# shoulder.net
KiCad netlist of a schematic drawn in EAGLE
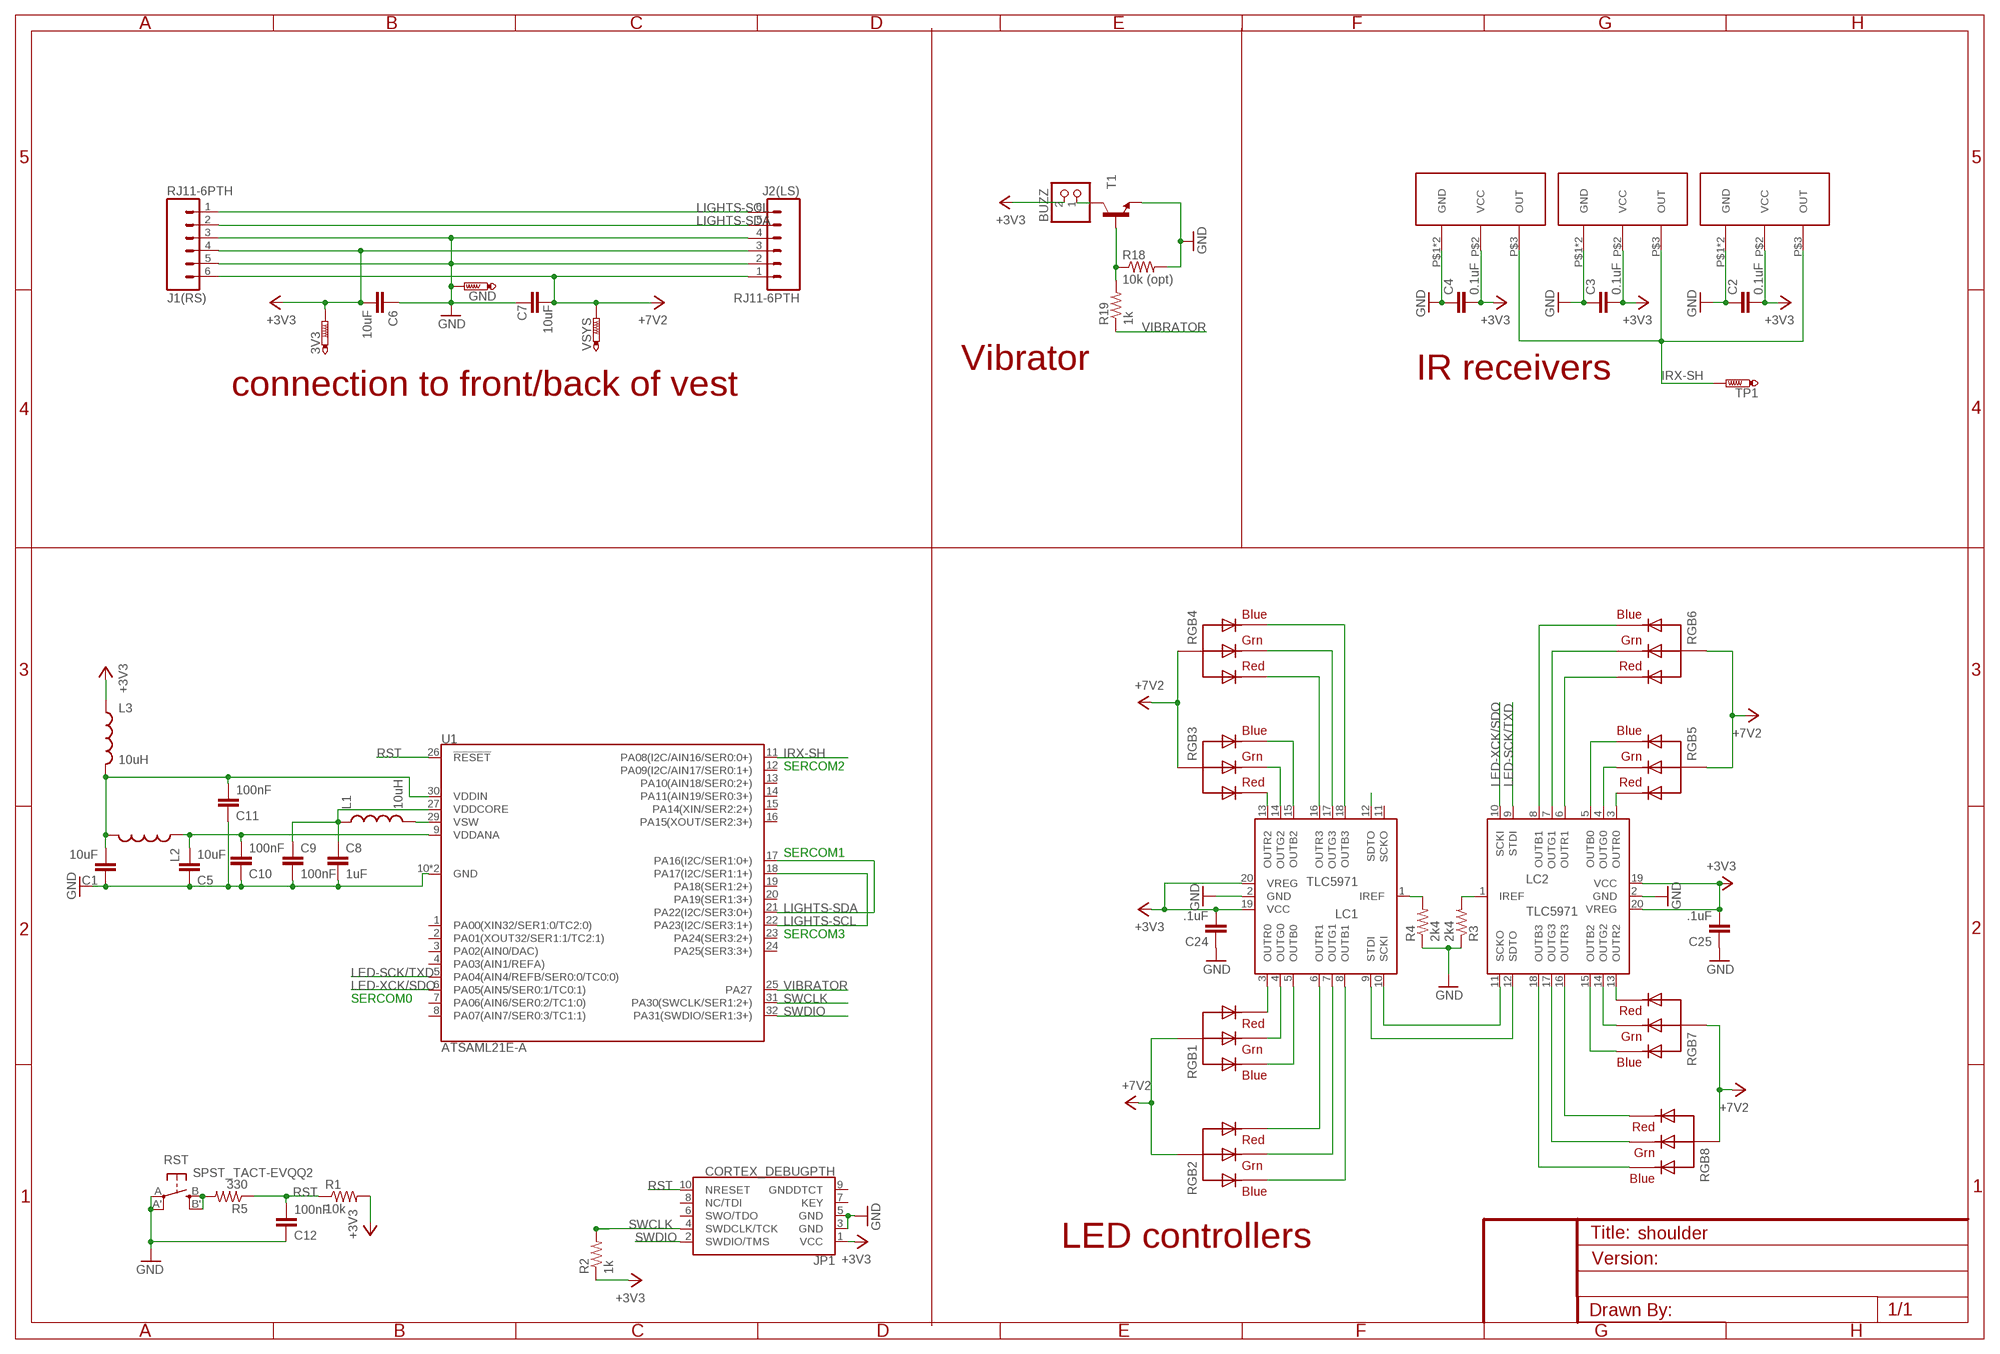
[diagram p0: schematic, sheet 1]

(export (version "E")
  (design (tool "Eeschema 10.0.6"))
  (components
    (comp (ref "3V3")
      (value "PTR1PAD1-17")
      (footprint "eagle-import:P1-17")
      (libsource (lib "eagle-import") (part "PTR1PAD1-17"))
    )
    (comp (ref "BUZZ")
      (value "JST_2PIN-THM")
      (footprint "eagle-import:JST-PH-2-THM")
      (libsource (lib "eagle-import") (part "JST_2PIN-THM"))
    )
    (comp (ref "C1")
      (value "10uF")
      (footprint "eagle-import:0603-CAP")
      (libsource (lib "eagle-import") (part "SparkFun-Passives_CAP0603-CAP"))
    )
    (comp (ref "C2")
      (value "0.1uF")
      (footprint "eagle-import:0603-CAP")
      (libsource (lib "eagle-import") (part "CAP0603-CAP"))
    )
    (comp (ref "C3")
      (value "0.1uF")
      (footprint "eagle-import:0603-CAP")
      (libsource (lib "eagle-import") (part "CAP0603-CAP"))
    )
    (comp (ref "C4")
      (value "0.1uF")
      (footprint "eagle-import:0603-CAP")
      (libsource (lib "eagle-import") (part "CAP0603-CAP"))
    )
    (comp (ref "C5")
      (value "10uF")
      (footprint "eagle-import:0603-CAP")
      (libsource (lib "eagle-import") (part "SparkFun-Passives_CAP0603-CAP"))
    )
    (comp (ref "C6")
      (value "10uF")
      (footprint "eagle-import:1206")
      (libsource (lib "eagle-import") (part "SparkFun-Passives_CAP1206"))
    )
    (comp (ref "C7")
      (value "10uF")
      (footprint "eagle-import:1206")
      (libsource (lib "eagle-import") (part "SparkFun-Passives_CAP1206"))
    )
    (comp (ref "C8")
      (value "1uF")
      (footprint "eagle-import:0603-CAP")
      (libsource (lib "eagle-import") (part "SparkFun-Passives_CAP0603-CAP"))
    )
    (comp (ref "C9")
      (value "100nF")
      (footprint "eagle-import:0603-CAP")
      (libsource (lib "eagle-import") (part "SparkFun-Passives_CAP0603-CAP"))
    )
    (comp (ref "C10")
      (value "100nF")
      (footprint "eagle-import:0603-CAP")
      (libsource (lib "eagle-import") (part "SparkFun-Passives_CAP0603-CAP"))
    )
    (comp (ref "C11")
      (value "100nF")
      (footprint "eagle-import:0603-CAP")
      (libsource (lib "eagle-import") (part "SparkFun-Passives_CAP0603-CAP"))
    )
    (comp (ref "C12")
      (value "100nF")
      (footprint "eagle-import:0603-CAP")
      (libsource (lib "eagle-import") (part "SparkFun-Passives_CAP0603-CAP"))
    )
    (comp (ref "C24")
      (value ".1uF")
      (footprint "eagle-import:0603-CAP")
      (libsource (lib "eagle-import") (part "CAP0603-CAP"))
    )
    (comp (ref "C25")
      (value ".1uF")
      (footprint "eagle-import:0603-CAP")
      (libsource (lib "eagle-import") (part "CAP0603-CAP"))
    )
    (comp (ref "GND")
      (value "PTR1PAD1-17")
      (footprint "eagle-import:P1-17")
      (libsource (lib "eagle-import") (part "PTR1PAD1-17"))
    )
    (comp (ref "J1(RS)")
      (value "RJ11-6PTH")
      (footprint "eagle-import:RJ11-6")
      (libsource (lib "eagle-import") (part "RJ11-6PTH"))
    )
    (comp (ref "J2(LS)")
      (value "RJ11-6PTH")
      (footprint "eagle-import:RJ11-6")
      (libsource (lib "eagle-import") (part "RJ11-6PTH"))
    )
    (comp (ref "JP1")
      (value "CORTEX_DEBUGPTH")
      (footprint "eagle-import:2X5-PTH-1.27MM")
      (libsource (lib "eagle-import") (part "CORTEX_DEBUGPTH"))
    )
    (comp (ref "L1")
      (value "10uH")
      (footprint "eagle-import:0805")
      (libsource (lib "eagle-import") (part "INDUCTOR0805"))
    )
    (comp (ref "L2")
      (value "INDUCTOR0603")
      (footprint "eagle-import:0603")
      (libsource (lib "eagle-import") (part "INDUCTOR0603"))
    )
    (comp (ref "L3")
      (value "10uH")
      (footprint "eagle-import:0805")
      (libsource (lib "eagle-import") (part "INDUCTOR0805"))
    )
    (comp (ref "LC1")
      (value "TLC5971")
      (footprint "eagle-import:SSOP20")
      (libsource (lib "eagle-import") (part "TLC5971"))
    )
    (comp (ref "LC2")
      (value "TLC5971")
      (footprint "eagle-import:SSOP20")
      (libsource (lib "eagle-import") (part "TLC5971"))
    )
    (comp (ref "R1")
      (value "10k")
      (footprint "eagle-import:0603-RES")
      (libsource (lib "eagle-import") (part "RESISTOR0603-RES"))
    )
    (comp (ref "R2")
      (value "1k")
      (footprint "eagle-import:0603-RES")
      (libsource (lib "eagle-import") (part "RESISTOR0603-RES"))
    )
    (comp (ref "R3")
      (value "2k4")
      (footprint "eagle-import:0603-RES")
      (libsource (lib "eagle-import") (part "RESISTOR0603-RES"))
    )
    (comp (ref "R4")
      (value "2k4")
      (footprint "eagle-import:0603-RES")
      (libsource (lib "eagle-import") (part "RESISTOR0603-RES"))
    )
    (comp (ref "R5")
      (value "330")
      (footprint "eagle-import:0603-RES")
      (libsource (lib "eagle-import") (part "RESISTOR0603-RES"))
    )
    (comp (ref "R18")
      (value "10k (opt)")
      (footprint "eagle-import:0603-RES")
      (libsource (lib "eagle-import") (part "RESISTOR0603-RES"))
    )
    (comp (ref "R19")
      (value "1k")
      (footprint "eagle-import:0603-RES")
      (libsource (lib "eagle-import") (part "RESISTOR0603-RES"))
    )
    (comp (ref "RGB1")
      (value "AVAGO-RGB-SMT")
      (footprint "eagle-import:AVAGO-SMT-RGB")
      (libsource (lib "eagle-import") (part "AVAGO-RGB-SMT"))
    )
    (comp (ref "RGB2")
      (value "AVAGO-RGB-SMT")
      (footprint "eagle-import:AVAGO-SMT-RGB")
      (libsource (lib "eagle-import") (part "AVAGO-RGB-SMT"))
    )
    (comp (ref "RGB3")
      (value "AVAGO-RGB-SMT")
      (footprint "eagle-import:AVAGO-SMT-RGB")
      (libsource (lib "eagle-import") (part "AVAGO-RGB-SMT"))
    )
    (comp (ref "RGB4")
      (value "AVAGO-RGB-SMT")
      (footprint "eagle-import:AVAGO-SMT-RGB")
      (libsource (lib "eagle-import") (part "AVAGO-RGB-SMT"))
    )
    (comp (ref "RGB5")
      (value "AVAGO-RGB-SMT")
      (footprint "eagle-import:AVAGO-SMT-RGB")
      (libsource (lib "eagle-import") (part "AVAGO-RGB-SMT"))
    )
    (comp (ref "RGB6")
      (value "AVAGO-RGB-SMT")
      (footprint "eagle-import:AVAGO-SMT-RGB")
      (libsource (lib "eagle-import") (part "AVAGO-RGB-SMT"))
    )
    (comp (ref "RGB7")
      (value "AVAGO-RGB-SMT")
      (footprint "eagle-import:AVAGO-SMT-RGB")
      (libsource (lib "eagle-import") (part "AVAGO-RGB-SMT"))
    )
    (comp (ref "RGB8")
      (value "AVAGO-RGB-SMT")
      (footprint "eagle-import:AVAGO-SMT-RGB")
      (libsource (lib "eagle-import") (part "AVAGO-RGB-SMT"))
    )
    (comp (ref "RST")
      (value "SPST_TACT-EVQQ2")
      (footprint "eagle-import:EVQ-Q2")
      (libsource (lib "eagle-import") (part "SPST_TACT-EVQQ2"))
    )
    (comp (ref "T1")
      (value "TRANSISTOR_NPNSOT23")
      (footprint "eagle-import:SOT23")
      (libsource (lib "eagle-import") (part "TRANSISTOR_NPNSOT23"))
    )
    (comp (ref "TP1")
      (value "PTR1PAD1-17")
      (footprint "eagle-import:P1-17")
      (libsource (lib "eagle-import") (part "PTR1PAD1-17"))
    )
    (comp (ref "U$1")
      (value "TSMP77000SIDE")
      (footprint "eagle-import:TSMP77000")
      (libsource (lib "eagle-import") (part "TSMP77000SIDE"))
    )
    (comp (ref "U$2")
      (value "TSMP77000SIDE")
      (footprint "eagle-import:TSMP77000")
      (libsource (lib "eagle-import") (part "TSMP77000SIDE"))
    )
    (comp (ref "U$3")
      (value "TSMP77000UP")
      (footprint "eagle-import:HEIMDALL-UP")
      (libsource (lib "eagle-import") (part "TSMP77000UP"))
    )
    (comp (ref "U1")
      (value "ATSAML21E-A")
      (footprint "eagle-import:TQFP-32-7X7-0.8MM")
      (libsource (lib "eagle-import") (part "ATSAML21E-A"))
    )
    (comp (ref "VSYS")
      (value "PTR1PAD1-17")
      (footprint "eagle-import:P1-17")
      (libsource (lib "eagle-import") (part "PTR1PAD1-17"))
    )
  )
  (nets
    (net (code "1") (name "+3V3") (class "Default")
      (node (ref "3V3") (pin "TP") (pinfunction "TP_TP") (pintype "input"))
      (node (ref "BUZZ") (pin "2") (pinfunction "1_2") (pintype "passive"))
      (node (ref "C2") (pin "2") (pinfunction "2_2") (pintype "passive"))
      (node (ref "C24") (pin "2") (pinfunction "2_2") (pintype "passive"))
      (node (ref "C25") (pin "2") (pinfunction "2_2") (pintype "passive"))
      (node (ref "C3") (pin "2") (pinfunction "2_2") (pintype "passive"))
      (node (ref "C4") (pin "2") (pinfunction "2_2") (pintype "passive"))
      (node (ref "C6") (pin "2") (pinfunction "2_2") (pintype "passive"))
      (node (ref "J1(RS)") (pin "4") (pinfunction "4_4") (pintype "passive"))
      (node (ref "J2(LS)") (pin "3") (pinfunction "3_3") (pintype "passive"))
      (node (ref "JP1") (pin "1") (pinfunction "VCC_1") (pintype "bidirectional"))
      (node (ref "L3") (pin "1") (pinfunction "1_1") (pintype "passive"))
      (node (ref "LC1") (pin "19") (pinfunction "VCC_19") (pintype "power_in"))
      (node (ref "LC1") (pin "20") (pinfunction "VREG_20") (pintype "passive"))
      (node (ref "LC2") (pin "19") (pinfunction "VCC_19") (pintype "power_in"))
      (node (ref "LC2") (pin "20") (pinfunction "VREG_20") (pintype "passive"))
      (node (ref "R1") (pin "2") (pinfunction "2_2") (pintype "passive"))
      (node (ref "R2") (pin "1") (pinfunction "1_1") (pintype "passive"))
      (node (ref "U$1") (pin "P$2") (pinfunction "VCC_P$2") (pintype "passive"))
      (node (ref "U$2") (pin "P$2") (pinfunction "VCC_P$2") (pintype "passive"))
      (node (ref "U$3") (pin "P$2") (pinfunction "VCC_P$2") (pintype "passive"))
    )
    (net (code "2") (name "/+7V2") (class "Default")
      (node (ref "C7") (pin "2") (pinfunction "2_2") (pintype "passive"))
      (node (ref "J1(RS)") (pin "6") (pinfunction "6_6") (pintype "passive"))
      (node (ref "J2(LS)") (pin "1") (pinfunction "1_1") (pintype "passive"))
      (node (ref "RGB1") (pin "P$4") (pinfunction "VCC_P$4") (pintype "bidirectional"))
      (node (ref "RGB1") (pin "P$5") (pinfunction "VCC_P$5") (pintype "bidirectional"))
      (node (ref "RGB1") (pin "P$6") (pinfunction "VCC_P$6") (pintype "bidirectional"))
      (node (ref "RGB2") (pin "P$4") (pinfunction "VCC_P$4") (pintype "bidirectional"))
      (node (ref "RGB2") (pin "P$5") (pinfunction "VCC_P$5") (pintype "bidirectional"))
      (node (ref "RGB2") (pin "P$6") (pinfunction "VCC_P$6") (pintype "bidirectional"))
      (node (ref "RGB3") (pin "P$4") (pinfunction "VCC_P$4") (pintype "bidirectional"))
      (node (ref "RGB3") (pin "P$5") (pinfunction "VCC_P$5") (pintype "bidirectional"))
      (node (ref "RGB3") (pin "P$6") (pinfunction "VCC_P$6") (pintype "bidirectional"))
      (node (ref "RGB4") (pin "P$4") (pinfunction "VCC_P$4") (pintype "bidirectional"))
      (node (ref "RGB4") (pin "P$5") (pinfunction "VCC_P$5") (pintype "bidirectional"))
      (node (ref "RGB4") (pin "P$6") (pinfunction "VCC_P$6") (pintype "bidirectional"))
      (node (ref "RGB5") (pin "P$4") (pinfunction "VCC_P$4") (pintype "bidirectional"))
      (node (ref "RGB5") (pin "P$5") (pinfunction "VCC_P$5") (pintype "bidirectional"))
      (node (ref "RGB5") (pin "P$6") (pinfunction "VCC_P$6") (pintype "bidirectional"))
      (node (ref "RGB6") (pin "P$4") (pinfunction "VCC_P$4") (pintype "bidirectional"))
      (node (ref "RGB6") (pin "P$5") (pinfunction "VCC_P$5") (pintype "bidirectional"))
      (node (ref "RGB6") (pin "P$6") (pinfunction "VCC_P$6") (pintype "bidirectional"))
      (node (ref "RGB7") (pin "P$4") (pinfunction "VCC_P$4") (pintype "bidirectional"))
      (node (ref "RGB7") (pin "P$5") (pinfunction "VCC_P$5") (pintype "bidirectional"))
      (node (ref "RGB7") (pin "P$6") (pinfunction "VCC_P$6") (pintype "bidirectional"))
      (node (ref "RGB8") (pin "P$4") (pinfunction "VCC_P$4") (pintype "bidirectional"))
      (node (ref "RGB8") (pin "P$5") (pinfunction "VCC_P$5") (pintype "bidirectional"))
      (node (ref "RGB8") (pin "P$6") (pinfunction "VCC_P$6") (pintype "bidirectional"))
      (node (ref "VSYS") (pin "TP") (pinfunction "TP_TP") (pintype "input"))
    )
    (net (code "3") (name "/IRX-SH") (class "Default")
      (node (ref "TP1") (pin "TP") (pinfunction "TP_TP") (pintype "input"))
      (node (ref "U$1") (pin "P$3") (pinfunction "OUT_P$3") (pintype "passive"))
      (node (ref "U$2") (pin "P$3") (pinfunction "OUT_P$3") (pintype "passive"))
      (node (ref "U$3") (pin "P$3") (pinfunction "OUT_P$3") (pintype "passive"))
      (node (ref "U1") (pin "11") (pinfunction "PA08(I2C/AIN16/SER0:0+)_11") (pintype "bidirectional"))
    )
    (net (code "4") (name "/LED-SCK{slash}TXD") (class "Default")
      (node (ref "LC2") (pin "9") (pinfunction "STDI_9") (pintype "bidirectional"))
      (node (ref "U1") (pin "5") (pinfunction "PA04(AIN4/REFB/SER0:0/TC0:0)_5") (pintype "bidirectional"))
    )
    (net (code "5") (name "/LED-XCK{slash}SDO") (class "Default")
      (node (ref "LC2") (pin "10") (pinfunction "SCKI_10") (pintype "bidirectional"))
      (node (ref "U1") (pin "6") (pinfunction "PA05(AIN5/SER0:1/TC0:1)_6") (pintype "bidirectional"))
    )
    (net (code "6") (name "/LIGHTS-SCL") (class "Default")
      (node (ref "J1(RS)") (pin "1") (pinfunction "1_1") (pintype "passive"))
      (node (ref "J2(LS)") (pin "6") (pinfunction "6_6") (pintype "passive"))
      (node (ref "U1") (pin "18") (pinfunction "PA17(I2C/SER1:1+)_18") (pintype "bidirectional"))
      (node (ref "U1") (pin "22") (pinfunction "PA23(I2C/SER3:1+)_22") (pintype "bidirectional"))
    )
    (net (code "7") (name "/LIGHTS-SDA") (class "Default")
      (node (ref "J1(RS)") (pin "2") (pinfunction "2_2") (pintype "passive"))
      (node (ref "J2(LS)") (pin "5") (pinfunction "5_5") (pintype "passive"))
      (node (ref "U1") (pin "17") (pinfunction "PA16(I2C/SER1:0+)_17") (pintype "bidirectional"))
      (node (ref "U1") (pin "21") (pinfunction "PA22(I2C/SER3:0+)_21") (pintype "bidirectional"))
    )
    (net (code "8") (name "/RST") (class "Default")
      (node (ref "C12") (pin "2") (pinfunction "2_2") (pintype "passive"))
      (node (ref "JP1") (pin "10") (pinfunction "NRESET_10") (pintype "bidirectional"))
      (node (ref "R1") (pin "1") (pinfunction "1_1") (pintype "passive"))
      (node (ref "R5") (pin "1") (pinfunction "1_1") (pintype "passive"))
      (node (ref "U1") (pin "26") (pinfunction "~{RESET}_26") (pintype "bidirectional"))
    )
    (net (code "9") (name "/SWCLK") (class "Default")
      (node (ref "JP1") (pin "4") (pinfunction "SWDCLK/TCK_4") (pintype "bidirectional"))
      (node (ref "R2") (pin "2") (pinfunction "2_2") (pintype "passive"))
      (node (ref "U1") (pin "31") (pinfunction "PA30(SWCLK/SER1:2+)_31") (pintype "bidirectional"))
    )
    (net (code "10") (name "/SWDIO") (class "Default")
      (node (ref "JP1") (pin "2") (pinfunction "SWDIO/TMS_2") (pintype "bidirectional"))
      (node (ref "U1") (pin "32") (pinfunction "PA31(SWDIO/SER1:3+)_32") (pintype "bidirectional"))
    )
    (net (code "11") (name "/VIBRATOR") (class "Default")
      (node (ref "R19") (pin "1") (pinfunction "1_1") (pintype "passive"))
      (node (ref "U1") (pin "25") (pinfunction "PA27_25") (pintype "bidirectional"))
    )
    (net (code "12") (name "GND") (class "Default")
      (node (ref "C1") (pin "1") (pinfunction "1_1") (pintype "passive"))
      (node (ref "C10") (pin "1") (pinfunction "1_1") (pintype "passive"))
      (node (ref "C11") (pin "1") (pinfunction "1_1") (pintype "passive"))
      (node (ref "C12") (pin "1") (pinfunction "1_1") (pintype "passive"))
      (node (ref "C2") (pin "1") (pinfunction "1_1") (pintype "passive"))
      (node (ref "C24") (pin "1") (pinfunction "1_1") (pintype "passive"))
      (node (ref "C25") (pin "1") (pinfunction "1_1") (pintype "passive"))
      (node (ref "C3") (pin "1") (pinfunction "1_1") (pintype "passive"))
      (node (ref "C4") (pin "1") (pinfunction "1_1") (pintype "passive"))
      (node (ref "C5") (pin "1") (pinfunction "1_1") (pintype "passive"))
      (node (ref "C6") (pin "1") (pinfunction "1_1") (pintype "passive"))
      (node (ref "C7") (pin "1") (pinfunction "1_1") (pintype "passive"))
      (node (ref "C8") (pin "2") (pinfunction "2_2") (pintype "passive"))
      (node (ref "C9") (pin "2") (pinfunction "2_2") (pintype "passive"))
      (node (ref "GND") (pin "TP") (pinfunction "TP_TP") (pintype "input"))
      (node (ref "J1(RS)") (pin "3") (pinfunction "3_3") (pintype "passive"))
      (node (ref "J1(RS)") (pin "5") (pinfunction "5_5") (pintype "passive"))
      (node (ref "J2(LS)") (pin "2") (pinfunction "2_2") (pintype "passive"))
      (node (ref "J2(LS)") (pin "4") (pinfunction "4_4") (pintype "passive"))
      (node (ref "JP1") (pin "3") (pinfunction "GND_3") (pintype "bidirectional"))
      (node (ref "JP1") (pin "5") (pinfunction "GND_5") (pintype "bidirectional"))
      (node (ref "LC1") (pin "2") (pinfunction "GND_2") (pintype "power_in"))
      (node (ref "LC2") (pin "2") (pinfunction "GND_2") (pintype "power_in"))
      (node (ref "R18") (pin "2") (pinfunction "2_2") (pintype "passive"))
      (node (ref "R3") (pin "1") (pinfunction "1_1") (pintype "passive"))
      (node (ref "R4") (pin "1") (pinfunction "1_1") (pintype "passive"))
      (node (ref "RST") (pin "A") (pinfunction "P_A") (pintype "passive"))
      (node (ref "RST") (pin "A'") (pinfunction "P1_A'") (pintype "passive"))
      (node (ref "T1") (pin "2") (pinfunction "E_2") (pintype "passive"))
      (node (ref "U$1") (pin "P$1") (pinfunction "GND_P$1") (pintype "passive"))
      (node (ref "U$1") (pin "P$4") (pinfunction "GND_P$4") (pintype "passive"))
      (node (ref "U$2") (pin "P$1") (pinfunction "GND_P$1") (pintype "passive"))
      (node (ref "U$2") (pin "P$4") (pinfunction "GND_P$4") (pintype "passive"))
      (node (ref "U$3") (pin "P$1") (pinfunction "GND_P$1") (pintype "passive"))
      (node (ref "U$3") (pin "P$4") (pinfunction "GND_P$4") (pintype "passive"))
      (node (ref "U1") (pin "10") (pinfunction "GND_10") (pintype "bidirectional"))
      (node (ref "U1") (pin "28") (pinfunction "GND_28") (pintype "bidirectional"))
    )
    (net (code "13") (name "Net-(BUZZ-2)") (class "Default")
      (node (ref "BUZZ") (pin "1") (pinfunction "2_1") (pintype "passive"))
      (node (ref "T1") (pin "3") (pinfunction "C_3") (pintype "passive"))
    )
    (net (code "14") (name "Net-(LC1-IREF)") (class "Default")
      (node (ref "LC1") (pin "1") (pinfunction "IREF_1") (pintype "bidirectional"))
      (node (ref "R4") (pin "2") (pinfunction "2_2") (pintype "passive"))
    )
    (net (code "15") (name "Net-(LC1-OUTB0)") (class "Default")
      (node (ref "LC1") (pin "5") (pinfunction "OUTB0_5") (pintype "bidirectional"))
      (node (ref "RGB1") (pin "P$1") (pinfunction "BLUE_P$1") (pintype "bidirectional"))
    )
    (net (code "16") (name "Net-(LC1-OUTB1)") (class "Default")
      (node (ref "LC1") (pin "8") (pinfunction "OUTB1_8") (pintype "bidirectional"))
      (node (ref "RGB2") (pin "P$1") (pinfunction "BLUE_P$1") (pintype "bidirectional"))
    )
    (net (code "17") (name "Net-(LC1-OUTB2)") (class "Default")
      (node (ref "LC1") (pin "15") (pinfunction "OUTB2_15") (pintype "bidirectional"))
      (node (ref "RGB3") (pin "P$1") (pinfunction "BLUE_P$1") (pintype "bidirectional"))
    )
    (net (code "18") (name "Net-(LC1-OUTB3)") (class "Default")
      (node (ref "LC1") (pin "18") (pinfunction "OUTB3_18") (pintype "bidirectional"))
      (node (ref "RGB4") (pin "P$1") (pinfunction "BLUE_P$1") (pintype "bidirectional"))
    )
    (net (code "19") (name "Net-(LC1-OUTG0)") (class "Default")
      (node (ref "LC1") (pin "4") (pinfunction "OUTG0_4") (pintype "bidirectional"))
      (node (ref "RGB1") (pin "P$2") (pinfunction "GREEN_P$2") (pintype "bidirectional"))
    )
    (net (code "20") (name "Net-(LC1-OUTG1)") (class "Default")
      (node (ref "LC1") (pin "7") (pinfunction "OUTG1_7") (pintype "bidirectional"))
      (node (ref "RGB2") (pin "P$2") (pinfunction "GREEN_P$2") (pintype "bidirectional"))
    )
    (net (code "21") (name "Net-(LC1-OUTG2)") (class "Default")
      (node (ref "LC1") (pin "14") (pinfunction "OUTG2_14") (pintype "bidirectional"))
      (node (ref "RGB3") (pin "P$2") (pinfunction "GREEN_P$2") (pintype "bidirectional"))
    )
    (net (code "22") (name "Net-(LC1-OUTG3)") (class "Default")
      (node (ref "LC1") (pin "17") (pinfunction "OUTG3_17") (pintype "bidirectional"))
      (node (ref "RGB4") (pin "P$2") (pinfunction "GREEN_P$2") (pintype "bidirectional"))
    )
    (net (code "23") (name "Net-(LC1-OUTR0)") (class "Default")
      (node (ref "LC1") (pin "3") (pinfunction "OUTR0_3") (pintype "bidirectional"))
      (node (ref "RGB1") (pin "P$3") (pinfunction "RED_P$3") (pintype "bidirectional"))
    )
    (net (code "24") (name "Net-(LC1-OUTR1)") (class "Default")
      (node (ref "LC1") (pin "6") (pinfunction "OUTR1_6") (pintype "bidirectional"))
      (node (ref "RGB2") (pin "P$3") (pinfunction "RED_P$3") (pintype "bidirectional"))
    )
    (net (code "25") (name "Net-(LC1-OUTR2)") (class "Default")
      (node (ref "LC1") (pin "13") (pinfunction "OUTR2_13") (pintype "bidirectional"))
      (node (ref "RGB3") (pin "P$3") (pinfunction "RED_P$3") (pintype "bidirectional"))
    )
    (net (code "26") (name "Net-(LC1-OUTR3)") (class "Default")
      (node (ref "LC1") (pin "16") (pinfunction "OUTR3_16") (pintype "bidirectional"))
      (node (ref "RGB4") (pin "P$3") (pinfunction "RED_P$3") (pintype "bidirectional"))
    )
    (net (code "27") (name "Net-(LC1-SCKI)") (class "Default")
      (node (ref "LC1") (pin "10") (pinfunction "SCKI_10") (pintype "bidirectional"))
      (node (ref "LC2") (pin "11") (pinfunction "SCKO_11") (pintype "bidirectional"))
    )
    (net (code "28") (name "Net-(LC1-STDI)") (class "Default")
      (node (ref "LC1") (pin "9") (pinfunction "STDI_9") (pintype "bidirectional"))
      (node (ref "LC2") (pin "12") (pinfunction "SDTO_12") (pintype "bidirectional"))
    )
    (net (code "29") (name "Net-(LC2-IREF)") (class "Default")
      (node (ref "LC2") (pin "1") (pinfunction "IREF_1") (pintype "bidirectional"))
      (node (ref "R3") (pin "2") (pinfunction "2_2") (pintype "passive"))
    )
    (net (code "30") (name "Net-(LC2-OUTB0)") (class "Default")
      (node (ref "LC2") (pin "5") (pinfunction "OUTB0_5") (pintype "bidirectional"))
      (node (ref "RGB5") (pin "P$1") (pinfunction "BLUE_P$1") (pintype "bidirectional"))
    )
    (net (code "31") (name "Net-(LC2-OUTB1)") (class "Default")
      (node (ref "LC2") (pin "8") (pinfunction "OUTB1_8") (pintype "bidirectional"))
      (node (ref "RGB6") (pin "P$1") (pinfunction "BLUE_P$1") (pintype "bidirectional"))
    )
    (net (code "32") (name "Net-(LC2-OUTB2)") (class "Default")
      (node (ref "LC2") (pin "15") (pinfunction "OUTB2_15") (pintype "bidirectional"))
      (node (ref "RGB7") (pin "P$1") (pinfunction "BLUE_P$1") (pintype "bidirectional"))
    )
    (net (code "33") (name "Net-(LC2-OUTB3)") (class "Default")
      (node (ref "LC2") (pin "18") (pinfunction "OUTB3_18") (pintype "bidirectional"))
      (node (ref "RGB8") (pin "P$1") (pinfunction "BLUE_P$1") (pintype "bidirectional"))
    )
    (net (code "34") (name "Net-(LC2-OUTG0)") (class "Default")
      (node (ref "LC2") (pin "4") (pinfunction "OUTG0_4") (pintype "bidirectional"))
      (node (ref "RGB5") (pin "P$2") (pinfunction "GREEN_P$2") (pintype "bidirectional"))
    )
    (net (code "35") (name "Net-(LC2-OUTG1)") (class "Default")
      (node (ref "LC2") (pin "7") (pinfunction "OUTG1_7") (pintype "bidirectional"))
      (node (ref "RGB6") (pin "P$2") (pinfunction "GREEN_P$2") (pintype "bidirectional"))
    )
    (net (code "36") (name "Net-(LC2-OUTG2)") (class "Default")
      (node (ref "LC2") (pin "14") (pinfunction "OUTG2_14") (pintype "bidirectional"))
      (node (ref "RGB7") (pin "P$2") (pinfunction "GREEN_P$2") (pintype "bidirectional"))
    )
    (net (code "37") (name "Net-(LC2-OUTG3)") (class "Default")
      (node (ref "LC2") (pin "17") (pinfunction "OUTG3_17") (pintype "bidirectional"))
      (node (ref "RGB8") (pin "P$2") (pinfunction "GREEN_P$2") (pintype "bidirectional"))
    )
    (net (code "38") (name "Net-(LC2-OUTR0)") (class "Default")
      (node (ref "LC2") (pin "3") (pinfunction "OUTR0_3") (pintype "bidirectional"))
      (node (ref "RGB5") (pin "P$3") (pinfunction "RED_P$3") (pintype "bidirectional"))
    )
    (net (code "39") (name "Net-(LC2-OUTR1)") (class "Default")
      (node (ref "LC2") (pin "6") (pinfunction "OUTR1_6") (pintype "bidirectional"))
      (node (ref "RGB6") (pin "P$3") (pinfunction "RED_P$3") (pintype "bidirectional"))
    )
    (net (code "40") (name "Net-(LC2-OUTR2)") (class "Default")
      (node (ref "LC2") (pin "13") (pinfunction "OUTR2_13") (pintype "bidirectional"))
      (node (ref "RGB7") (pin "P$3") (pinfunction "RED_P$3") (pintype "bidirectional"))
    )
    (net (code "41") (name "Net-(LC2-OUTR3)") (class "Default")
      (node (ref "LC2") (pin "16") (pinfunction "OUTR3_16") (pintype "bidirectional"))
      (node (ref "RGB8") (pin "P$3") (pinfunction "RED_P$3") (pintype "bidirectional"))
    )
    (net (code "42") (name "Net-(RST-S)") (class "Default")
      (node (ref "R5") (pin "2") (pinfunction "2_2") (pintype "passive"))
      (node (ref "RST") (pin "B") (pinfunction "S_B") (pintype "passive"))
      (node (ref "RST") (pin "B'") (pinfunction "S1_B'") (pintype "passive"))
    )
    (net (code "43") (name "Net-(T1-B)") (class "Default")
      (node (ref "R18") (pin "1") (pinfunction "1_1") (pintype "passive"))
      (node (ref "R19") (pin "2") (pinfunction "2_2") (pintype "passive"))
      (node (ref "T1") (pin "1") (pinfunction "B_1") (pintype "passive"))
    )
    (net (code "44") (name "Net-(U1-VDDANA)") (class "Default")
      (node (ref "C10") (pin "2") (pinfunction "2_2") (pintype "passive"))
      (node (ref "C5") (pin "2") (pinfunction "2_2") (pintype "passive"))
      (node (ref "L2") (pin "1") (pinfunction "1_1") (pintype "passive"))
      (node (ref "U1") (pin "9") (pinfunction "VDDANA_9") (pintype "bidirectional"))
    )
    (net (code "45") (name "Net-(U1-VDDCORE)") (class "Default")
      (node (ref "C8") (pin "1") (pinfunction "1_1") (pintype "passive"))
      (node (ref "C9") (pin "1") (pinfunction "1_1") (pintype "passive"))
      (node (ref "L1") (pin "1") (pinfunction "1_1") (pintype "passive"))
      (node (ref "U1") (pin "27") (pinfunction "VDDCORE_27") (pintype "bidirectional"))
    )
    (net (code "46") (name "Net-(U1-VDDIN)") (class "Default")
      (node (ref "C1") (pin "2") (pinfunction "2_2") (pintype "passive"))
      (node (ref "C11") (pin "2") (pinfunction "2_2") (pintype "passive"))
      (node (ref "L2") (pin "2") (pinfunction "2_2") (pintype "passive"))
      (node (ref "L3") (pin "2") (pinfunction "2_2") (pintype "passive"))
      (node (ref "U1") (pin "30") (pinfunction "VDDIN_30") (pintype "bidirectional"))
    )
    (net (code "47") (name "Net-(U1-VSW)") (class "Default")
      (node (ref "L1") (pin "2") (pinfunction "2_2") (pintype "passive"))
      (node (ref "U1") (pin "29") (pinfunction "VSW_29") (pintype "bidirectional"))
    )
    (net (code "48") (name "unconnected-(JP1-GNDDTCT-Pad9)") (class "Default")
      (node (ref "JP1") (pin "9") (pinfunction "GNDDTCT_9") (pintype "bidirectional"))
    )
    (net (code "49") (name "unconnected-(JP1-KEY-Pad7)") (class "Default")
      (node (ref "JP1") (pin "7") (pinfunction "KEY_7") (pintype "bidirectional"))
    )
    (net (code "50") (name "unconnected-(JP1-NC{slash}TDI-Pad8)") (class "Default")
      (node (ref "JP1") (pin "8") (pinfunction "NC/TDI_8") (pintype "bidirectional"))
    )
    (net (code "51") (name "unconnected-(JP1-SWO{slash}TDO-Pad6)") (class "Default")
      (node (ref "JP1") (pin "6") (pinfunction "SWO/TDO_6") (pintype "bidirectional"))
    )
    (net (code "52") (name "unconnected-(LC1-SCKO-Pad11)") (class "Default")
      (node (ref "LC1") (pin "11") (pinfunction "SCKO_11") (pintype "bidirectional"))
    )
    (net (code "53") (name "unconnected-(LC1-SDTO-Pad12)") (class "Default")
      (node (ref "LC1") (pin "12") (pinfunction "SDTO_12") (pintype "bidirectional"))
    )
    (net (code "54") (name "unconnected-(U1-PA00(XIN32{slash}SER1:0{slash}TC2:0)-Pad1)") (class "Default")
      (node (ref "U1") (pin "1") (pinfunction "PA00(XIN32/SER1:0/TC2:0)_1") (pintype "bidirectional"))
    )
    (net (code "55") (name "unconnected-(U1-PA01(XOUT32{slash}SER1:1{slash}TC2:1)-Pad2)") (class "Default")
      (node (ref "U1") (pin "2") (pinfunction "PA01(XOUT32/SER1:1/TC2:1)_2") (pintype "bidirectional"))
    )
    (net (code "56") (name "unconnected-(U1-PA02(AIN0{slash}DAC)-Pad3)") (class "Default")
      (node (ref "U1") (pin "3") (pinfunction "PA02(AIN0/DAC)_3") (pintype "bidirectional"))
    )
    (net (code "57") (name "unconnected-(U1-PA03(AIN1{slash}REFA)-Pad4)") (class "Default")
      (node (ref "U1") (pin "4") (pinfunction "PA03(AIN1/REFA)_4") (pintype "bidirectional"))
    )
    (net (code "58") (name "unconnected-(U1-PA06(AIN6{slash}SER0:2{slash}TC1:0)-Pad7)") (class "Default")
      (node (ref "U1") (pin "7") (pinfunction "PA06(AIN6/SER0:2/TC1:0)_7") (pintype "bidirectional"))
    )
    (net (code "59") (name "unconnected-(U1-PA07(AIN7{slash}SER0:3{slash}TC1:1)-Pad8)") (class "Default")
      (node (ref "U1") (pin "8") (pinfunction "PA07(AIN7/SER0:3/TC1:1)_8") (pintype "bidirectional"))
    )
    (net (code "60") (name "unconnected-(U1-PA09(I2C{slash}AIN17{slash}SER0:1+)-Pad12)") (class "Default")
      (node (ref "U1") (pin "12") (pinfunction "PA09(I2C/AIN17/SER0:1+)_12") (pintype "bidirectional"))
    )
    (net (code "61") (name "unconnected-(U1-PA10(AIN18{slash}SER0:2+)-Pad13)") (class "Default")
      (node (ref "U1") (pin "13") (pinfunction "PA10(AIN18/SER0:2+)_13") (pintype "bidirectional"))
    )
    (net (code "62") (name "unconnected-(U1-PA11(AIN19{slash}SER0:3+)-Pad14)") (class "Default")
      (node (ref "U1") (pin "14") (pinfunction "PA11(AIN19/SER0:3+)_14") (pintype "bidirectional"))
    )
    (net (code "63") (name "unconnected-(U1-PA14(XIN{slash}SER2:2+)-Pad15)") (class "Default")
      (node (ref "U1") (pin "15") (pinfunction "PA14(XIN/SER2:2+)_15") (pintype "bidirectional"))
    )
    (net (code "64") (name "unconnected-(U1-PA15(XOUT{slash}SER2:3+)-Pad16)") (class "Default")
      (node (ref "U1") (pin "16") (pinfunction "PA15(XOUT/SER2:3+)_16") (pintype "bidirectional"))
    )
    (net (code "65") (name "unconnected-(U1-PA18(SER1:2+)-Pad19)") (class "Default")
      (node (ref "U1") (pin "19") (pinfunction "PA18(SER1:2+)_19") (pintype "bidirectional"))
    )
    (net (code "66") (name "unconnected-(U1-PA19(SER1:3+)-Pad20)") (class "Default")
      (node (ref "U1") (pin "20") (pinfunction "PA19(SER1:3+)_20") (pintype "bidirectional"))
    )
    (net (code "67") (name "unconnected-(U1-PA24(SER3:2+)-Pad23)") (class "Default")
      (node (ref "U1") (pin "23") (pinfunction "PA24(SER3:2+)_23") (pintype "bidirectional"))
    )
    (net (code "68") (name "unconnected-(U1-PA25(SER3:3+)-Pad24)") (class "Default")
      (node (ref "U1") (pin "24") (pinfunction "PA25(SER3:3+)_24") (pintype "bidirectional"))
    )
  )
)
